# S0-energy-meter-switch-v1_1.net
KiCad netlist of a schematic drawn in EAGLE
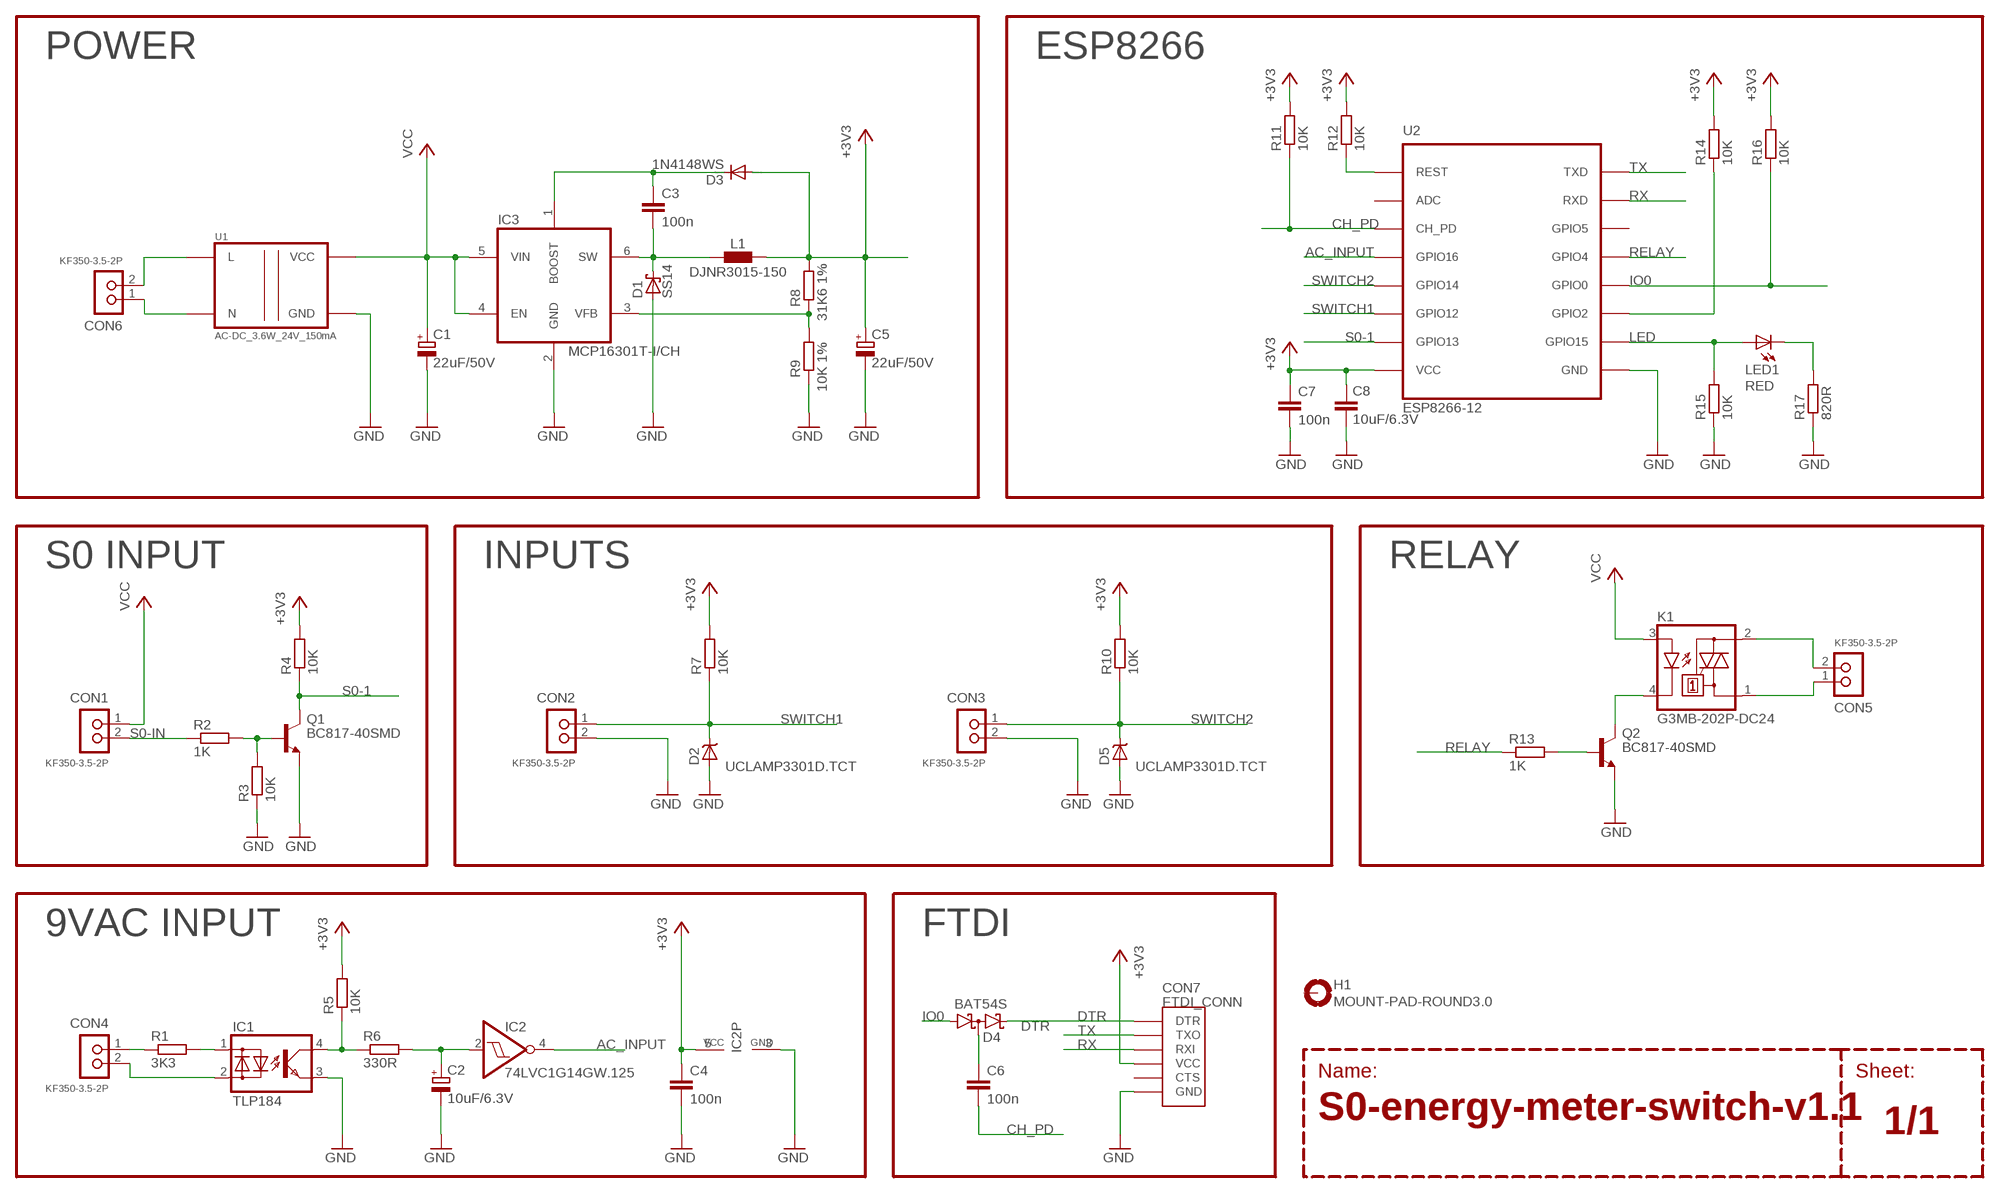
[diagram p0: schematic, sheet 1]

(export (version "E")
  (design (tool "Eeschema 10.0.6"))
  (components
    (comp (ref "C1")
      (value "22uF/50V")
      (footprint "eagle-import:PANASONIC_C")
      (libsource (lib "eagle-import") (part "CPOL-EUC"))
    )
    (comp (ref "C2")
      (value "10uF/6.3V")
      (footprint "eagle-import:CT3528")
      (libsource (lib "eagle-import") (part "CPOL-EUCT3528"))
    )
    (comp (ref "C3")
      (value "100n")
      (footprint "eagle-import:C0805")
      (libsource (lib "eagle-import") (part "rcl_334_C-EUC0805"))
    )
    (comp (ref "C4")
      (value "100n")
      (footprint "eagle-import:C0805")
      (libsource (lib "eagle-import") (part "rcl_334_C-EUC0805"))
    )
    (comp (ref "C5")
      (value "22uF/50V")
      (footprint "eagle-import:PANASONIC_C")
      (libsource (lib "eagle-import") (part "CPOL-EUC"))
    )
    (comp (ref "C6")
      (value "100n")
      (footprint "eagle-import:C0805")
      (libsource (lib "eagle-import") (part "C-EUC0805"))
    )
    (comp (ref "C7")
      (value "100n")
      (footprint "eagle-import:C0805")
      (libsource (lib "eagle-import") (part "rcl_334_C-EUC0805"))
    )
    (comp (ref "C8")
      (value "10uF/6.3V")
      (footprint "eagle-import:C0805")
      (libsource (lib "eagle-import") (part "rcl_334_C-EUC0805"))
    )
    (comp (ref "CON1")
      (value "KF350-3.5-2P")
      (footprint "eagle-import:KF350-3.50-2P")
      (libsource (lib "eagle-import") (part "KF350-3.5-2P"))
    )
    (comp (ref "CON2")
      (value "KF350-3.5-2P")
      (footprint "eagle-import:KF350-3.50-2P")
      (libsource (lib "eagle-import") (part "KF350-3.5-2P"))
    )
    (comp (ref "CON3")
      (value "KF350-3.5-2P")
      (footprint "eagle-import:KF350-3.50-2P")
      (libsource (lib "eagle-import") (part "KF350-3.5-2P"))
    )
    (comp (ref "CON4")
      (value "KF350-3.5-2P")
      (footprint "eagle-import:KF350-3.50-2P")
      (libsource (lib "eagle-import") (part "KF350-3.5-2P"))
    )
    (comp (ref "CON5")
      (value "KF350-3.5-2P")
      (footprint "eagle-import:KF350-3.50-2P")
      (libsource (lib "eagle-import") (part "KF350-3.5-2P"))
    )
    (comp (ref "CON6")
      (value "KF350-3.5-2P")
      (footprint "eagle-import:KF350-3.50-2P")
      (libsource (lib "eagle-import") (part "KF350-3.5-2P"))
    )
    (comp (ref "CON7")
      (value "FTDI_CONN")
      (footprint "eagle-import:FTDI")
      (libsource (lib "eagle-import") (part "FTDI_CONN"))
    )
    (comp (ref "D1")
      (value "SS14")
      (footprint "eagle-import:DO214AC")
      (libsource (lib "eagle-import") (part "SS?14"))
    )
    (comp (ref "D2")
      (value "UCLAMP3301D.TCT")
      (footprint "eagle-import:SOD323")
      (libsource (lib "eagle-import") (part "UCLAMP3301?.TCTD"))
    )
    (comp (ref "D3")
      (value "1N4148WS")
      (footprint "eagle-import:SOD323")
      (libsource (lib "eagle-import") (part "1N4148WS"))
    )
    (comp (ref "D4")
      (value "BAT54S")
      (footprint "eagle-import:SOT23")
      (libsource (lib "eagle-import") (part "BAT54S"))
    )
    (comp (ref "D5")
      (value "UCLAMP3301D.TCT")
      (footprint "eagle-import:SOD323")
      (libsource (lib "eagle-import") (part "UCLAMP3301?.TCTD"))
    )
    (comp (ref "H1")
      (value "MOUNT-PAD-ROUND3.0")
      (footprint "eagle-import:3,0-PAD")
      (libsource (lib "eagle-import") (part "MOUNT-PAD-ROUND3.0"))
    )
    (comp (ref "IC1")
      (value "TLP184")
      (footprint "eagle-import:SOP04")
      (libsource (lib "eagle-import") (part "TLP184"))
    )
    (comp (ref "IC2")
      (value "74LVC1G14GW.125")
      (footprint "eagle-import:SC70-5")
      (libsource (lib "eagle-import") (part "741G14DCKLVC"))
    )
    (comp (ref "IC3")
      (value "MCP16301T-I/CH")
      (footprint "eagle-import:SOT23-6")
      (libsource (lib "eagle-import") (part "MCP16301T-I/?CH"))
    )
    (comp (ref "K1")
      (value "G3MB-202P-DC24")
      (footprint "eagle-import:G3MB")
      (libsource (lib "eagle-import") (part "G3MB-202P?-DC24"))
    )
    (comp (ref "L1")
      (value "DJNR3015-150")
      (footprint "eagle-import:L3015")
      (libsource (lib "eagle-import") (part "DJNR?-3015150"))
    )
    (comp (ref "LED1")
      (value "RED")
      (footprint "eagle-import:LED0805")
      (libsource (lib "eagle-import") (part "LED0805"))
    )
    (comp (ref "Q1")
      (value "BC817-40SMD")
      (footprint "eagle-import:SOT23-BEC")
      (libsource (lib "eagle-import") (part "BC817SMD-40"))
    )
    (comp (ref "Q2")
      (value "BC817-40SMD")
      (footprint "eagle-import:SOT23-BEC")
      (libsource (lib "eagle-import") (part "BC817SMD-40"))
    )
    (comp (ref "R1")
      (value "3K3")
      (footprint "eagle-import:R1206")
      (libsource (lib "eagle-import") (part "R-EU_R1206"))
    )
    (comp (ref "R2")
      (value "1K")
      (footprint "eagle-import:R0805")
      (libsource (lib "eagle-import") (part "R-EU_R0805"))
    )
    (comp (ref "R3")
      (value "10K")
      (footprint "eagle-import:R0805")
      (libsource (lib "eagle-import") (part "R-EU_R0805"))
    )
    (comp (ref "R4")
      (value "10K")
      (footprint "eagle-import:R0805")
      (libsource (lib "eagle-import") (part "R-EU_R0805"))
    )
    (comp (ref "R5")
      (value "10K")
      (footprint "eagle-import:R0805")
      (libsource (lib "eagle-import") (part "R-EU_R0805"))
    )
    (comp (ref "R6")
      (value "330R")
      (footprint "eagle-import:R0805")
      (libsource (lib "eagle-import") (part "R-EU_R0805"))
    )
    (comp (ref "R7")
      (value "10K")
      (footprint "eagle-import:R0805")
      (libsource (lib "eagle-import") (part "R-EU_R0805"))
    )
    (comp (ref "R8")
      (value "31K6 1%")
      (footprint "eagle-import:R0805")
      (libsource (lib "eagle-import") (part "R-EU_R0805"))
    )
    (comp (ref "R9")
      (value "10K 1%")
      (footprint "eagle-import:R0805")
      (libsource (lib "eagle-import") (part "R-EU_R0805"))
    )
    (comp (ref "R10")
      (value "10K")
      (footprint "eagle-import:R0805")
      (libsource (lib "eagle-import") (part "R-EU_R0805"))
    )
    (comp (ref "R11")
      (value "10K")
      (footprint "eagle-import:R0805")
      (libsource (lib "eagle-import") (part "R-EU_R0805"))
    )
    (comp (ref "R12")
      (value "10K")
      (footprint "eagle-import:R0805")
      (libsource (lib "eagle-import") (part "R-EU_R0805"))
    )
    (comp (ref "R13")
      (value "1K")
      (footprint "eagle-import:R0805")
      (libsource (lib "eagle-import") (part "R-EU_R0805"))
    )
    (comp (ref "R14")
      (value "10K")
      (footprint "eagle-import:R0805")
      (libsource (lib "eagle-import") (part "R-EU_R0805"))
    )
    (comp (ref "R15")
      (value "10K")
      (footprint "eagle-import:R0805")
      (libsource (lib "eagle-import") (part "R-EU_R0805"))
    )
    (comp (ref "R16")
      (value "10K")
      (footprint "eagle-import:R0805")
      (libsource (lib "eagle-import") (part "R-EU_R0805"))
    )
    (comp (ref "R17")
      (value "820R")
      (footprint "eagle-import:R0805")
      (libsource (lib "eagle-import") (part "R-EU_R0805"))
    )
    (comp (ref "U1")
      (value "AC-DC_3.6W_24V_150mA")
      (footprint "eagle-import:AC_DC_24V_150MA")
      (libsource (lib "eagle-import") (part "AC-DC_?3.6W"))
    )
    (comp (ref "U2")
      (value "ESP8266-12")
      (footprint "eagle-import:ESP-12")
      (libsource (lib "eagle-import") (part "ESP8266-12"))
    )
  )
  (nets
    (net (code "1") (name "+3V3") (class "Default")
      (node (ref "C4") (pin "1") (pinfunction "1_1") (pintype "passive"))
      (node (ref "C5") (pin "+") (pinfunction "+_+") (pintype "passive"))
      (node (ref "C7") (pin "1") (pinfunction "1_1") (pintype "passive"))
      (node (ref "C8") (pin "1") (pinfunction "1_1") (pintype "passive"))
      (node (ref "CON7") (pin "P$4") (pinfunction "VCC_P$4") (pintype "bidirectional"))
      (node (ref "D3") (pin "A") (pinfunction "A_A") (pintype "passive"))
      (node (ref "IC2") (pin "5") (pinfunction "VCC_5") (pintype "power_in"))
      (node (ref "L1") (pin "1") (pinfunction "1_1") (pintype "passive"))
      (node (ref "R10") (pin "2") (pinfunction "2_2") (pintype "passive"))
      (node (ref "R11") (pin "2") (pinfunction "2_2") (pintype "passive"))
      (node (ref "R12") (pin "2") (pinfunction "2_2") (pintype "passive"))
      (node (ref "R14") (pin "2") (pinfunction "2_2") (pintype "passive"))
      (node (ref "R16") (pin "2") (pinfunction "2_2") (pintype "passive"))
      (node (ref "R4") (pin "2") (pinfunction "2_2") (pintype "passive"))
      (node (ref "R5") (pin "2") (pinfunction "2_2") (pintype "passive"))
      (node (ref "R7") (pin "2") (pinfunction "2_2") (pintype "passive"))
      (node (ref "R8") (pin "2") (pinfunction "2_2") (pintype "passive"))
      (node (ref "U2") (pin "VCC") (pinfunction "VCC_VCC") (pintype "power_in"))
    )
    (net (code "2") (name "/AC_INPUT") (class "Default")
      (node (ref "IC2") (pin "4") (pinfunction "O_4") (pintype "output"))
      (node (ref "U2") (pin "GPIO16") (pinfunction "GPIO16_GPIO16") (pintype "bidirectional"))
    )
    (net (code "3") (name "/CH_PD") (class "Default")
      (node (ref "C6") (pin "2") (pinfunction "2_2") (pintype "passive"))
      (node (ref "R11") (pin "1") (pinfunction "1_1") (pintype "passive"))
      (node (ref "U2") (pin "CH_PD") (pinfunction "CH_PD_CH_PD") (pintype "power_in"))
    )
    (net (code "4") (name "/DTR") (class "Default")
      (node (ref "CON7") (pin "P$1") (pinfunction "DTR_P$1") (pintype "bidirectional"))
      (node (ref "D4") (pin "2") (pinfunction "C2_2") (pintype "passive"))
    )
    (net (code "5") (name "/IO0") (class "Default")
      (node (ref "D4") (pin "1") (pinfunction "A1_1") (pintype "passive"))
      (node (ref "R16") (pin "1") (pinfunction "1_1") (pintype "passive"))
      (node (ref "U2") (pin "GPIO0") (pinfunction "GPIO0_GPIO0") (pintype "bidirectional"))
    )
    (net (code "6") (name "/LED") (class "Default")
      (node (ref "LED1") (pin "A") (pinfunction "A_A") (pintype "passive"))
      (node (ref "R15") (pin "2") (pinfunction "2_2") (pintype "passive"))
      (node (ref "U2") (pin "GPIO15") (pinfunction "GPIO15_GPIO15") (pintype "bidirectional"))
    )
    (net (code "7") (name "/RELAY") (class "Default")
      (node (ref "R13") (pin "1") (pinfunction "1_1") (pintype "passive"))
      (node (ref "U2") (pin "GPIO4") (pinfunction "GPIO4_GPIO4") (pintype "bidirectional"))
    )
    (net (code "8") (name "/RX") (class "Default")
      (node (ref "CON7") (pin "P$3") (pinfunction "RXI_P$3") (pintype "bidirectional"))
      (node (ref "U2") (pin "RXD") (pinfunction "RXD_RXD") (pintype "bidirectional"))
    )
    (net (code "9") (name "/S0-1") (class "Default")
      (node (ref "Q1") (pin "C") (pinfunction "C_C") (pintype "passive"))
      (node (ref "R4") (pin "1") (pinfunction "1_1") (pintype "passive"))
      (node (ref "U2") (pin "GPIO13") (pinfunction "GPIO13_GPIO13") (pintype "bidirectional"))
    )
    (net (code "10") (name "/S0-IN") (class "Default")
      (node (ref "CON1") (pin "2") (pinfunction "2_2") (pintype "passive"))
      (node (ref "R2") (pin "1") (pinfunction "1_1") (pintype "passive"))
    )
    (net (code "11") (name "/SWITCH1") (class "Default")
      (node (ref "CON2") (pin "1") (pinfunction "1_1") (pintype "passive"))
      (node (ref "D2") (pin "C") (pinfunction "C_C") (pintype "passive"))
      (node (ref "R7") (pin "1") (pinfunction "1_1") (pintype "passive"))
      (node (ref "U2") (pin "GPIO12") (pinfunction "GPIO12_GPIO12") (pintype "bidirectional"))
    )
    (net (code "12") (name "/SWITCH2") (class "Default")
      (node (ref "CON3") (pin "1") (pinfunction "1_1") (pintype "passive"))
      (node (ref "D5") (pin "C") (pinfunction "C_C") (pintype "passive"))
      (node (ref "R10") (pin "1") (pinfunction "1_1") (pintype "passive"))
      (node (ref "U2") (pin "GPIO14") (pinfunction "GPIO14_GPIO14") (pintype "bidirectional"))
    )
    (net (code "13") (name "/TX") (class "Default")
      (node (ref "CON7") (pin "P$2") (pinfunction "TXO_P$2") (pintype "bidirectional"))
      (node (ref "U2") (pin "TXD") (pinfunction "TXD_TXD") (pintype "bidirectional"))
    )
    (net (code "14") (name "GND") (class "Default")
      (node (ref "C1") (pin "-") (pinfunction "-_-") (pintype "passive"))
      (node (ref "C2") (pin "-") (pinfunction "-_-") (pintype "passive"))
      (node (ref "C4") (pin "2") (pinfunction "2_2") (pintype "passive"))
      (node (ref "C5") (pin "-") (pinfunction "-_-") (pintype "passive"))
      (node (ref "C7") (pin "2") (pinfunction "2_2") (pintype "passive"))
      (node (ref "C8") (pin "2") (pinfunction "2_2") (pintype "passive"))
      (node (ref "CON2") (pin "2") (pinfunction "2_2") (pintype "passive"))
      (node (ref "CON3") (pin "2") (pinfunction "2_2") (pintype "passive"))
      (node (ref "CON7") (pin "P$6") (pinfunction "GND_P$6") (pintype "bidirectional"))
      (node (ref "D1") (pin "A") (pinfunction "A_A") (pintype "passive"))
      (node (ref "D2") (pin "A") (pinfunction "A_A") (pintype "passive"))
      (node (ref "D5") (pin "A") (pinfunction "A_A") (pintype "passive"))
      (node (ref "IC1") (pin "3") (pinfunction "EMIT_3") (pintype "passive"))
      (node (ref "IC2") (pin "3") (pinfunction "GND_3") (pintype "power_in"))
      (node (ref "IC3") (pin "2") (pinfunction "GND_2") (pintype "power_in"))
      (node (ref "Q1") (pin "E") (pinfunction "E_E") (pintype "passive"))
      (node (ref "Q2") (pin "E") (pinfunction "E_E") (pintype "passive"))
      (node (ref "R15") (pin "1") (pinfunction "1_1") (pintype "passive"))
      (node (ref "R17") (pin "1") (pinfunction "1_1") (pintype "passive"))
      (node (ref "R3") (pin "1") (pinfunction "1_1") (pintype "passive"))
      (node (ref "R9") (pin "1") (pinfunction "1_1") (pintype "passive"))
      (node (ref "U1") (pin "GND") (pinfunction "GND_GND") (pintype "power_in"))
      (node (ref "U2") (pin "GND") (pinfunction "GND_GND") (pintype "power_in"))
    )
    (net (code "15") (name "Net-(CON4-Pad1)") (class "Default")
      (node (ref "CON4") (pin "1") (pinfunction "1_1") (pintype "passive"))
      (node (ref "R1") (pin "1") (pinfunction "1_1") (pintype "passive"))
    )
    (net (code "16") (name "Net-(CON6-Pad1)") (class "Default")
      (node (ref "CON6") (pin "1") (pinfunction "1_1") (pintype "passive"))
      (node (ref "U1") (pin "N") (pinfunction "N_N") (pintype "power_in"))
    )
    (net (code "17") (name "Net-(CON6-Pad2)") (class "Default")
      (node (ref "CON6") (pin "2") (pinfunction "2_2") (pintype "passive"))
      (node (ref "U1") (pin "L") (pinfunction "L_L") (pintype "power_in"))
    )
    (net (code "18") (name "Net-(D4-C1A2)") (class "Default")
      (node (ref "C6") (pin "1") (pinfunction "1_1") (pintype "passive"))
      (node (ref "D4") (pin "3") (pinfunction "C1A2_3") (pintype "passive"))
    )
    (net (code "19") (name "Net-(IC1-A)") (class "Default")
      (node (ref "IC1") (pin "1") (pinfunction "A_1") (pintype "passive"))
      (node (ref "R1") (pin "2") (pinfunction "2_2") (pintype "passive"))
    )
    (net (code "20") (name "Net-(IC1-C)") (class "Default")
      (node (ref "CON4") (pin "2") (pinfunction "2_2") (pintype "passive"))
      (node (ref "IC1") (pin "2") (pinfunction "C_2") (pintype "passive"))
    )
    (net (code "21") (name "Net-(IC1-COL)") (class "Default")
      (node (ref "IC1") (pin "4") (pinfunction "COL_4") (pintype "passive"))
      (node (ref "R5") (pin "1") (pinfunction "1_1") (pintype "passive"))
      (node (ref "R6") (pin "1") (pinfunction "1_1") (pintype "passive"))
    )
    (net (code "22") (name "Net-(IC2A-I)") (class "Default")
      (node (ref "C2") (pin "+") (pinfunction "+_+") (pintype "passive"))
      (node (ref "IC2") (pin "2") (pinfunction "I_2") (pintype "input"))
      (node (ref "R6") (pin "2") (pinfunction "2_2") (pintype "passive"))
    )
    (net (code "23") (name "Net-(IC3-BOOST)") (class "Default")
      (node (ref "C3") (pin "1") (pinfunction "1_1") (pintype "passive"))
      (node (ref "D3") (pin "C") (pinfunction "C_C") (pintype "passive"))
      (node (ref "IC3") (pin "1") (pinfunction "BOOST_1") (pintype "passive"))
    )
    (net (code "24") (name "Net-(IC3-SW)") (class "Default")
      (node (ref "C3") (pin "2") (pinfunction "2_2") (pintype "passive"))
      (node (ref "D1") (pin "C") (pinfunction "C_C") (pintype "passive"))
      (node (ref "IC3") (pin "6") (pinfunction "SW_6") (pintype "output"))
      (node (ref "L1") (pin "2") (pinfunction "2_2") (pintype "passive"))
    )
    (net (code "25") (name "Net-(IC3-VFB)") (class "Default")
      (node (ref "IC3") (pin "3") (pinfunction "VFB_3") (pintype "input"))
      (node (ref "R8") (pin "1") (pinfunction "1_1") (pintype "passive"))
      (node (ref "R9") (pin "2") (pinfunction "2_2") (pintype "passive"))
    )
    (net (code "26") (name "Net-(K1-A1)") (class "Default")
      (node (ref "CON5") (pin "1") (pinfunction "1_1") (pintype "passive"))
      (node (ref "K1") (pin "1") (pinfunction "A1_1") (pintype "passive"))
    )
    (net (code "27") (name "Net-(K1-A2)") (class "Default")
      (node (ref "CON5") (pin "2") (pinfunction "2_2") (pintype "passive"))
      (node (ref "K1") (pin "2") (pinfunction "A2_2") (pintype "passive"))
    )
    (net (code "28") (name "Net-(K1-C)") (class "Default")
      (node (ref "K1") (pin "4") (pinfunction "C_4") (pintype "passive"))
      (node (ref "Q2") (pin "C") (pinfunction "C_C") (pintype "passive"))
    )
    (net (code "29") (name "Net-(LED1-PadC)") (class "Default")
      (node (ref "LED1") (pin "C") (pinfunction "C_C") (pintype "passive"))
      (node (ref "R17") (pin "2") (pinfunction "2_2") (pintype "passive"))
    )
    (net (code "30") (name "Net-(Q1-PadB)") (class "Default")
      (node (ref "Q1") (pin "B") (pinfunction "B_B") (pintype "passive"))
      (node (ref "R2") (pin "2") (pinfunction "2_2") (pintype "passive"))
      (node (ref "R3") (pin "2") (pinfunction "2_2") (pintype "passive"))
    )
    (net (code "31") (name "Net-(Q2-PadB)") (class "Default")
      (node (ref "Q2") (pin "B") (pinfunction "B_B") (pintype "passive"))
      (node (ref "R13") (pin "2") (pinfunction "2_2") (pintype "passive"))
    )
    (net (code "32") (name "Net-(R12-Pad1)") (class "Default")
      (node (ref "R12") (pin "1") (pinfunction "1_1") (pintype "passive"))
      (node (ref "U2") (pin "REST") (pinfunction "REST_REST") (pintype "bidirectional"))
    )
    (net (code "33") (name "Net-(R14-Pad1)") (class "Default")
      (node (ref "R14") (pin "1") (pinfunction "1_1") (pintype "passive"))
      (node (ref "U2") (pin "GPIO2") (pinfunction "GPIO2_GPIO2") (pintype "bidirectional"))
    )
    (net (code "34") (name "VCC") (class "Default")
      (node (ref "C1") (pin "+") (pinfunction "+_+") (pintype "passive"))
      (node (ref "CON1") (pin "1") (pinfunction "1_1") (pintype "passive"))
      (node (ref "IC3") (pin "4") (pinfunction "EN_4") (pintype "input"))
      (node (ref "IC3") (pin "5") (pinfunction "VIN_5") (pintype "power_in"))
      (node (ref "K1") (pin "3") (pinfunction "A_3") (pintype "passive"))
      (node (ref "U1") (pin "VCC") (pinfunction "VCC_VCC") (pintype "power_in"))
    )
    (net (code "35") (name "unconnected-(CON7-CTS-PadP$5)") (class "Default")
      (node (ref "CON7") (pin "P$5") (pinfunction "CTS_P$5") (pintype "bidirectional"))
    )
    (net (code "36") (name "unconnected-(H1-MOUNT-PadB3,0)") (class "Default")
      (node (ref "H1") (pin "B3,0") (pinfunction "MOUNT_B3,0") (pintype "passive"))
    )
    (net (code "37") (name "unconnected-(U2-PadADC)") (class "Default")
      (node (ref "U2") (pin "ADC") (pinfunction "ADC_ADC") (pintype "bidirectional"))
    )
    (net (code "38") (name "unconnected-(U2-PadGPIO5)") (class "Default")
      (node (ref "U2") (pin "GPIO5") (pinfunction "GPIO5_GPIO5") (pintype "bidirectional"))
    )
  )
)
